# ActiveMoCapDeck_pre.net
KiCad netlist of a schematic drawn in EasyEDA Pro
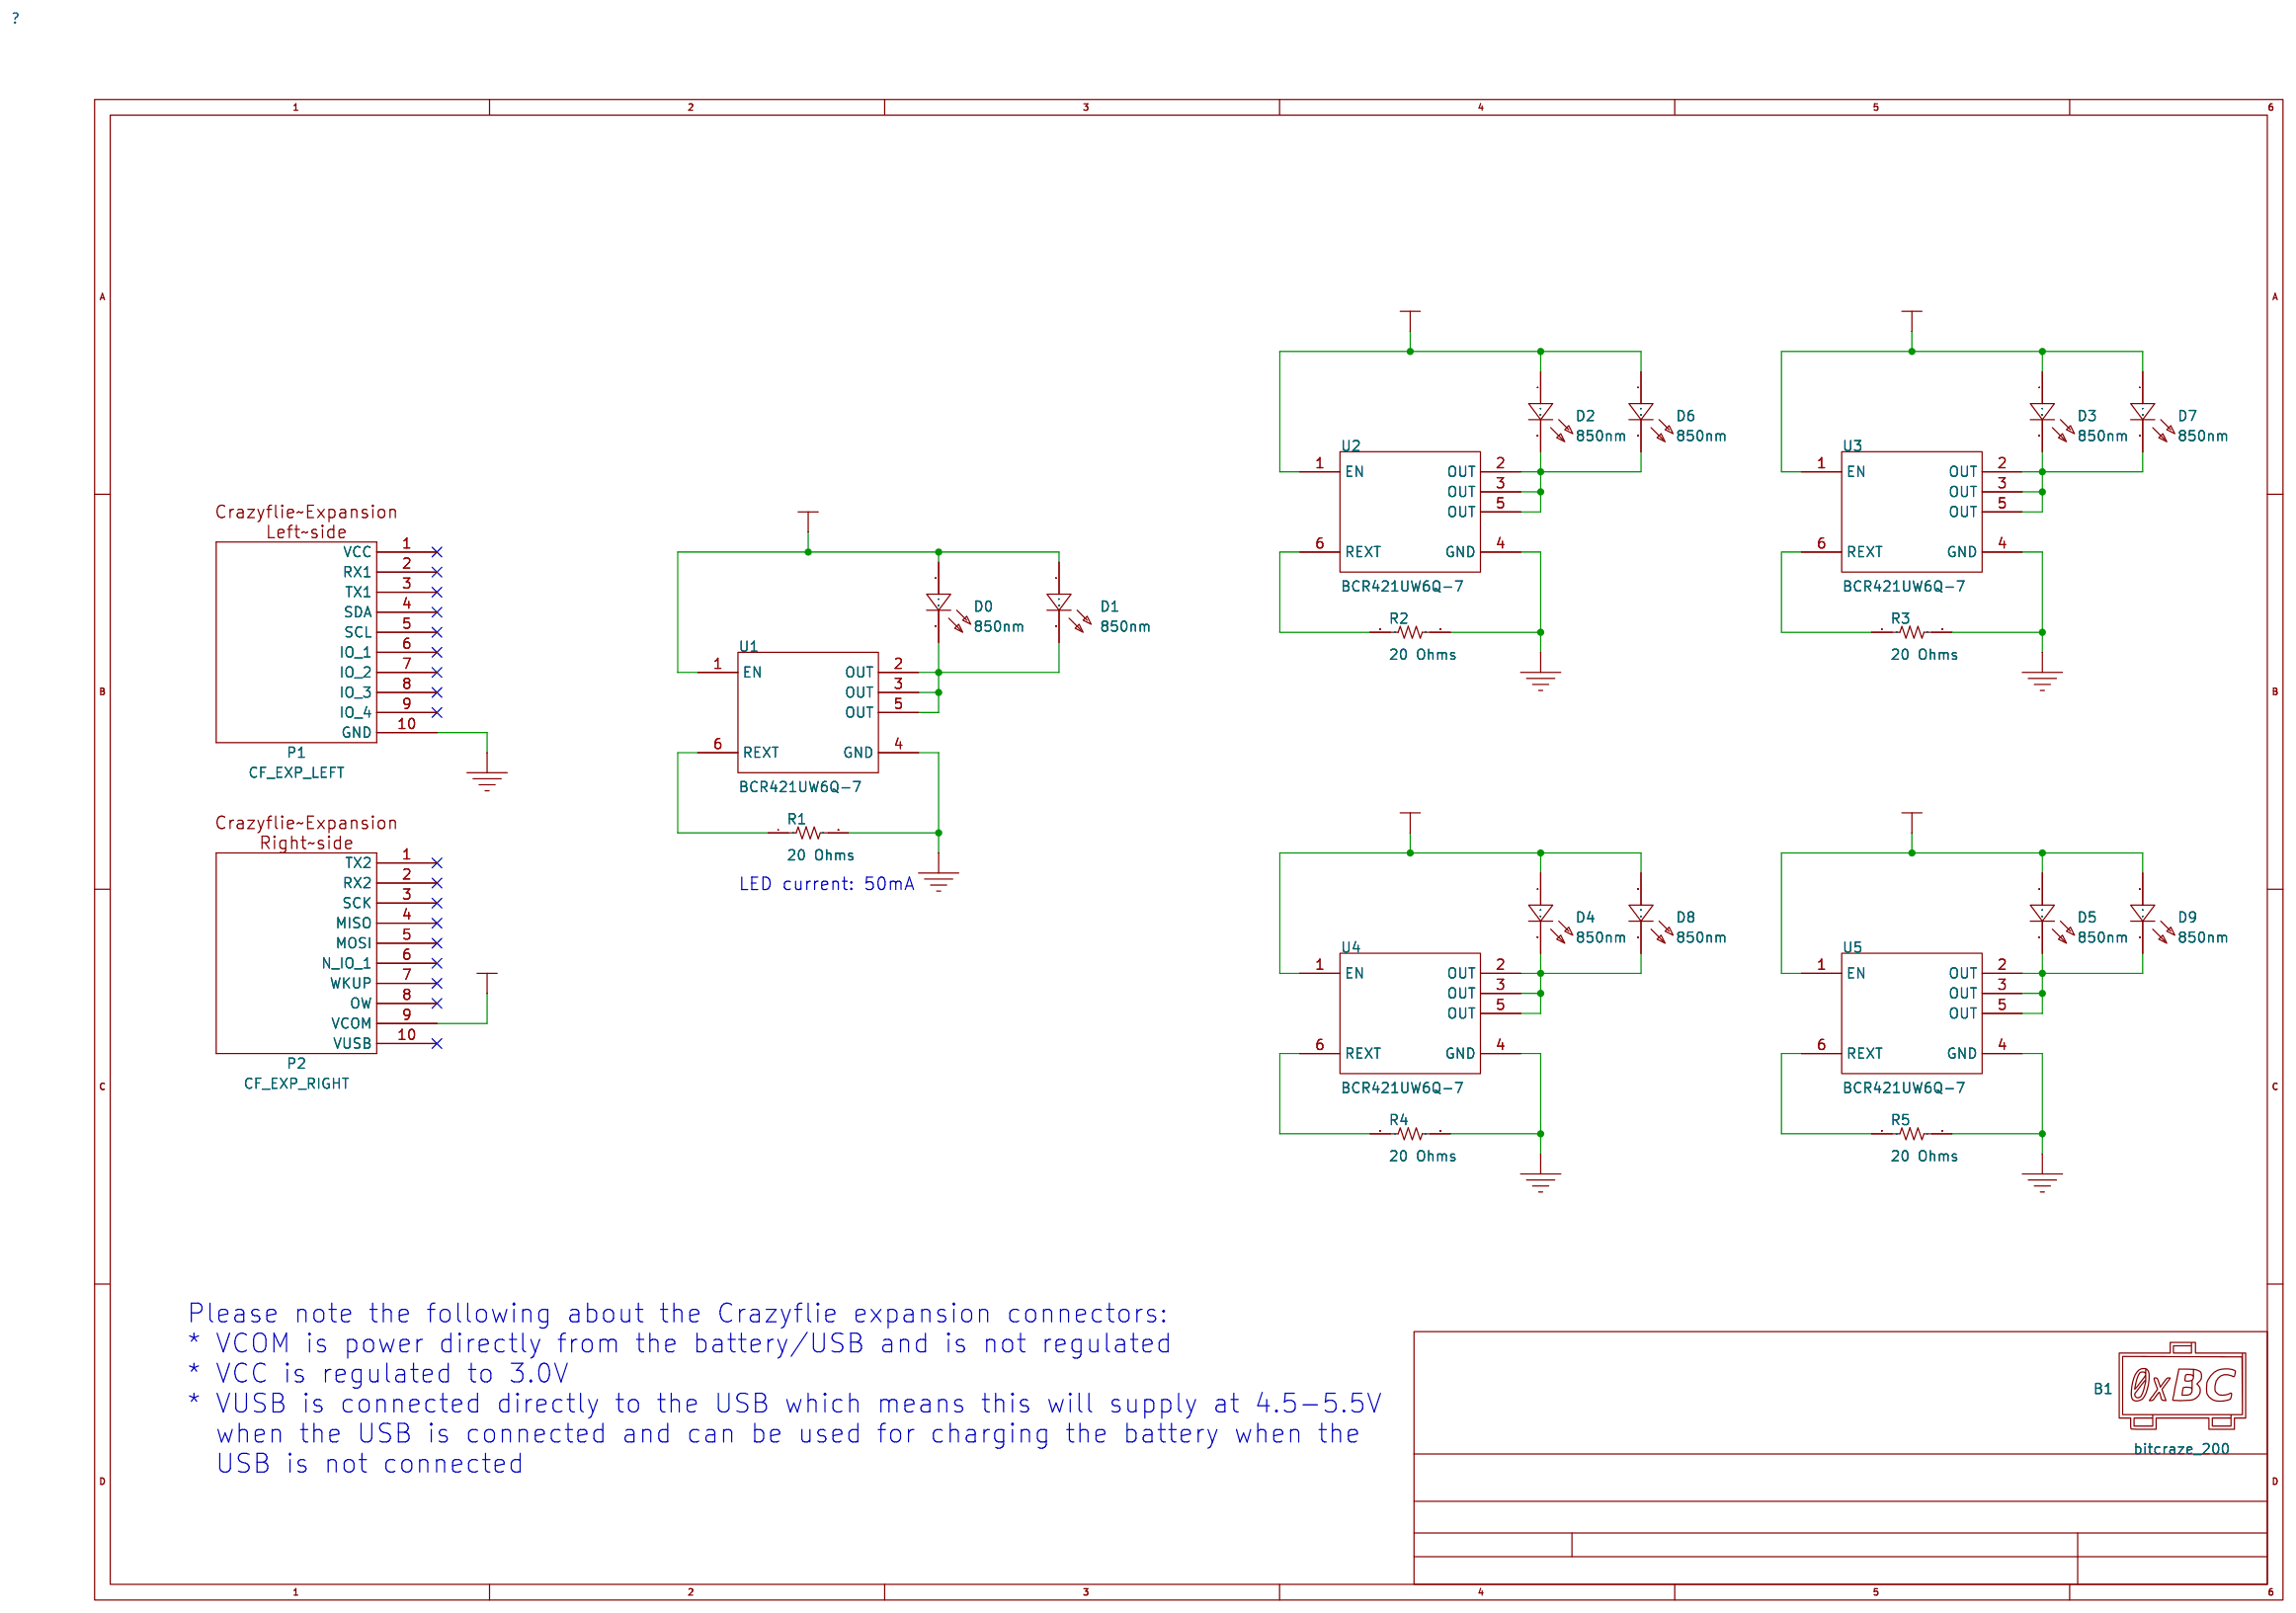
[diagram p0: schematic sheet]

(export (version "E")
  (design (tool "Eeschema 10.0.6"))
  (components
    (comp (ref "B1") (value "bitcraze_200") (libsource (lib "easyedapro") (part "bitcraze_200")))
    (comp (ref "D0")
      (value "Red")
      (description "LED RED SMD")
      (fields (field (name "Manufacturer") "Citizen"))
      (libsource (lib "easyedapro") (part "LED"))
    )
    (comp (ref "D1")
      (value "Red")
      (description "LED RED SMD")
      (fields (field (name "Manufacturer") "Citizen"))
      (libsource (lib "easyedapro") (part "LED"))
    )
    (comp (ref "D2")
      (value "Red")
      (description "LED RED SMD")
      (fields (field (name "Manufacturer") "Citizen"))
      (libsource (lib "easyedapro") (part "LED"))
    )
    (comp (ref "D3")
      (value "Red")
      (description "LED RED SMD")
      (fields (field (name "Manufacturer") "Citizen"))
      (libsource (lib "easyedapro") (part "LED"))
    )
    (comp (ref "D4")
      (value "Red")
      (description "LED RED SMD")
      (fields (field (name "Manufacturer") "Citizen"))
      (libsource (lib "easyedapro") (part "LED"))
    )
    (comp (ref "D5")
      (value "Red")
      (description "LED RED SMD")
      (fields (field (name "Manufacturer") "Citizen"))
      (libsource (lib "easyedapro") (part "LED"))
    )
    (comp (ref "D6")
      (value "Red")
      (description "LED RED SMD")
      (fields (field (name "Manufacturer") "Citizen"))
      (libsource (lib "easyedapro") (part "LED"))
    )
    (comp (ref "D7")
      (value "Red")
      (description "LED RED SMD")
      (fields (field (name "Manufacturer") "Citizen"))
      (libsource (lib "easyedapro") (part "LED"))
    )
    (comp (ref "D8")
      (value "Red")
      (description "LED RED SMD")
      (fields (field (name "Manufacturer") "Citizen"))
      (libsource (lib "easyedapro") (part "LED"))
    )
    (comp (ref "D9")
      (value "Red")
      (description "LED RED SMD")
      (fields (field (name "Manufacturer") "Citizen"))
      (libsource (lib "easyedapro") (part "LED"))
    )
    (comp (ref "P1") (value "CF_EXP_LEFT") (libsource (lib "easyedapro") (part "CF_EXP_LEFT")))
    (comp (ref "P2") (value "CF_EXP_RIGHT") (libsource (lib "easyedapro") (part "CF_EXP_RIGHT")))
    (comp (ref "R1")
      (value "20 Ohms")
      (description "RES 20 OHM 5% 1/10W 0603")
      (fields (field (name "Manufacturer") "Yageo"))
      (libsource (lib "easyedapro") (part "Resistor"))
    )
    (comp (ref "R2")
      (value "20 Ohms")
      (description "RES 20 OHM 5% 1/10W 0603")
      (fields (field (name "Manufacturer") "Yageo"))
      (libsource (lib "easyedapro") (part "Resistor"))
    )
    (comp (ref "R3")
      (value "20 Ohms")
      (description "RES 20 OHM 5% 1/10W 0603")
      (fields (field (name "Manufacturer") "Yageo"))
      (libsource (lib "easyedapro") (part "Resistor"))
    )
    (comp (ref "R4")
      (value "20 Ohms")
      (description "RES 20 OHM 5% 1/10W 0603")
      (fields (field (name "Manufacturer") "Yageo"))
      (libsource (lib "easyedapro") (part "Resistor"))
    )
    (comp (ref "R5")
      (value "20 Ohms")
      (description "RES 20 OHM 5% 1/10W 0603")
      (fields (field (name "Manufacturer") "Yageo"))
      (libsource (lib "easyedapro") (part "Resistor"))
    )
    (comp (ref "U1")
      (value "BCR421UW6Q-7")
      (description "TRANSISTOR LED DRIVER SOT26 T&amp;R")
      (fields (field (name "Manufacturer") "Diodes Inc."))
      (libsource (lib "easyedapro") (part "ad914be0572bb629e6d009380f5a8f4"))
    )
    (comp (ref "U2")
      (value "BCR421UW6Q-7")
      (description "TRANSISTOR LED DRIVER SOT26 T&amp;R")
      (fields (field (name "Manufacturer") "Diodes Inc."))
      (libsource (lib "easyedapro") (part "ad914be0572bb629e6d009380f5a8f4"))
    )
    (comp (ref "U3")
      (value "BCR421UW6Q-7")
      (description "TRANSISTOR LED DRIVER SOT26 T&amp;R")
      (fields (field (name "Manufacturer") "Diodes Inc."))
      (libsource (lib "easyedapro") (part "ad914be0572bb629e6d009380f5a8f4"))
    )
    (comp (ref "U4")
      (value "BCR421UW6Q-7")
      (description "TRANSISTOR LED DRIVER SOT26 T&amp;R")
      (fields (field (name "Manufacturer") "Diodes Inc."))
      (libsource (lib "easyedapro") (part "ad914be0572bb629e6d009380f5a8f4"))
    )
    (comp (ref "U5")
      (value "BCR421UW6Q-7")
      (description "TRANSISTOR LED DRIVER SOT26 T&amp;R")
      (fields (field (name "Manufacturer") "Diodes Inc."))
      (libsource (lib "easyedapro") (part "ad914be0572bb629e6d009380f5a8f4"))
    )
  )
  (nets
    (net (code "1") (name "GND") (class "Default")
      (node (ref "P1") (pin "10") (pinfunction "GND_10") (pintype "unspecified"))
      (node (ref "R1") (pin "2") (pinfunction "2_2") (pintype "unspecified"))
      (node (ref "R2") (pin "2") (pinfunction "2_2") (pintype "unspecified"))
      (node (ref "R3") (pin "2") (pinfunction "2_2") (pintype "unspecified"))
      (node (ref "R4") (pin "2") (pinfunction "2_2") (pintype "unspecified"))
      (node (ref "R5") (pin "2") (pinfunction "2_2") (pintype "unspecified"))
      (node (ref "U1") (pin "4") (pinfunction "GND_4") (pintype "unspecified"))
      (node (ref "U2") (pin "4") (pinfunction "GND_4") (pintype "unspecified"))
      (node (ref "U3") (pin "4") (pinfunction "GND_4") (pintype "unspecified"))
      (node (ref "U4") (pin "4") (pinfunction "GND_4") (pintype "unspecified"))
      (node (ref "U5") (pin "4") (pinfunction "GND_4") (pintype "unspecified"))
    )
    (net (code "2") (name "Net-(D0-Pad2)") (class "Default")
      (node (ref "D0") (pin "2") (pinfunction "2_2") (pintype "unspecified"))
      (node (ref "D1") (pin "2") (pinfunction "2_2") (pintype "unspecified"))
      (node (ref "U1") (pin "2") (pinfunction "OUT_2") (pintype "unspecified"))
      (node (ref "U1") (pin "3") (pinfunction "OUT_3") (pintype "unspecified"))
      (node (ref "U1") (pin "5") (pinfunction "OUT_5") (pintype "unspecified"))
    )
    (net (code "3") (name "Net-(D2-Pad2)") (class "Default")
      (node (ref "D2") (pin "2") (pinfunction "2_2") (pintype "unspecified"))
      (node (ref "D6") (pin "2") (pinfunction "2_2") (pintype "unspecified"))
      (node (ref "U2") (pin "2") (pinfunction "OUT_2") (pintype "unspecified"))
      (node (ref "U2") (pin "3") (pinfunction "OUT_3") (pintype "unspecified"))
      (node (ref "U2") (pin "5") (pinfunction "OUT_5") (pintype "unspecified"))
    )
    (net (code "4") (name "Net-(D3-Pad2)") (class "Default")
      (node (ref "D3") (pin "2") (pinfunction "2_2") (pintype "unspecified"))
      (node (ref "D7") (pin "2") (pinfunction "2_2") (pintype "unspecified"))
      (node (ref "U3") (pin "2") (pinfunction "OUT_2") (pintype "unspecified"))
      (node (ref "U3") (pin "3") (pinfunction "OUT_3") (pintype "unspecified"))
      (node (ref "U3") (pin "5") (pinfunction "OUT_5") (pintype "unspecified"))
    )
    (net (code "5") (name "Net-(D4-Pad2)") (class "Default")
      (node (ref "D4") (pin "2") (pinfunction "2_2") (pintype "unspecified"))
      (node (ref "D8") (pin "2") (pinfunction "2_2") (pintype "unspecified"))
      (node (ref "U4") (pin "2") (pinfunction "OUT_2") (pintype "unspecified"))
      (node (ref "U4") (pin "3") (pinfunction "OUT_3") (pintype "unspecified"))
      (node (ref "U4") (pin "5") (pinfunction "OUT_5") (pintype "unspecified"))
    )
    (net (code "6") (name "Net-(D5-Pad2)") (class "Default")
      (node (ref "D5") (pin "2") (pinfunction "2_2") (pintype "unspecified"))
      (node (ref "D9") (pin "2") (pinfunction "2_2") (pintype "unspecified"))
      (node (ref "U5") (pin "2") (pinfunction "OUT_2") (pintype "unspecified"))
      (node (ref "U5") (pin "3") (pinfunction "OUT_3") (pintype "unspecified"))
      (node (ref "U5") (pin "5") (pinfunction "OUT_5") (pintype "unspecified"))
    )
    (net (code "7") (name "Net-(U1-REXT)") (class "Default")
      (node (ref "R1") (pin "1") (pinfunction "1_1") (pintype "unspecified"))
      (node (ref "U1") (pin "6") (pinfunction "REXT_6") (pintype "unspecified"))
    )
    (net (code "8") (name "Net-(U2-REXT)") (class "Default")
      (node (ref "R2") (pin "1") (pinfunction "1_1") (pintype "unspecified"))
      (node (ref "U2") (pin "6") (pinfunction "REXT_6") (pintype "unspecified"))
    )
    (net (code "9") (name "Net-(U3-REXT)") (class "Default")
      (node (ref "R3") (pin "1") (pinfunction "1_1") (pintype "unspecified"))
      (node (ref "U3") (pin "6") (pinfunction "REXT_6") (pintype "unspecified"))
    )
    (net (code "10") (name "Net-(U4-REXT)") (class "Default")
      (node (ref "R4") (pin "1") (pinfunction "1_1") (pintype "unspecified"))
      (node (ref "U4") (pin "6") (pinfunction "REXT_6") (pintype "unspecified"))
    )
    (net (code "11") (name "Net-(U5-REXT)") (class "Default")
      (node (ref "R5") (pin "1") (pinfunction "1_1") (pintype "unspecified"))
      (node (ref "U5") (pin "6") (pinfunction "REXT_6") (pintype "unspecified"))
    )
    (net (code "12") (name "VCOM") (class "Default")
      (node (ref "D0") (pin "1") (pinfunction "1_1") (pintype "unspecified"))
      (node (ref "D1") (pin "1") (pinfunction "1_1") (pintype "unspecified"))
      (node (ref "D2") (pin "1") (pinfunction "1_1") (pintype "unspecified"))
      (node (ref "D3") (pin "1") (pinfunction "1_1") (pintype "unspecified"))
      (node (ref "D4") (pin "1") (pinfunction "1_1") (pintype "unspecified"))
      (node (ref "D5") (pin "1") (pinfunction "1_1") (pintype "unspecified"))
      (node (ref "D6") (pin "1") (pinfunction "1_1") (pintype "unspecified"))
      (node (ref "D7") (pin "1") (pinfunction "1_1") (pintype "unspecified"))
      (node (ref "D8") (pin "1") (pinfunction "1_1") (pintype "unspecified"))
      (node (ref "D9") (pin "1") (pinfunction "1_1") (pintype "unspecified"))
      (node (ref "P2") (pin "9") (pinfunction "VCOM_9") (pintype "unspecified"))
      (node (ref "U1") (pin "1") (pinfunction "EN_1") (pintype "input"))
      (node (ref "U2") (pin "1") (pinfunction "EN_1") (pintype "input"))
      (node (ref "U3") (pin "1") (pinfunction "EN_1") (pintype "input"))
      (node (ref "U4") (pin "1") (pinfunction "EN_1") (pintype "input"))
      (node (ref "U5") (pin "1") (pinfunction "EN_1") (pintype "input"))
    )
    (net (code "13") (name "unconnected-(P1-IO_1-Pad6)") (class "Default")
      (node (ref "P1") (pin "6") (pinfunction "IO_1_6") (pintype "unspecified+no_connect"))
    )
    (net (code "14") (name "unconnected-(P1-IO_2-Pad7)") (class "Default")
      (node (ref "P1") (pin "7") (pinfunction "IO_2_7") (pintype "unspecified+no_connect"))
    )
    (net (code "15") (name "unconnected-(P1-IO_3-Pad8)") (class "Default")
      (node (ref "P1") (pin "8") (pinfunction "IO_3_8") (pintype "unspecified+no_connect"))
    )
    (net (code "16") (name "unconnected-(P1-IO_4-Pad9)") (class "Default")
      (node (ref "P1") (pin "9") (pinfunction "IO_4_9") (pintype "unspecified+no_connect"))
    )
    (net (code "17") (name "unconnected-(P1-RX1-Pad2)") (class "Default")
      (node (ref "P1") (pin "2") (pinfunction "RX1_2") (pintype "unspecified+no_connect"))
    )
    (net (code "18") (name "unconnected-(P1-SCL-Pad5)") (class "Default")
      (node (ref "P1") (pin "5") (pinfunction "SCL_5") (pintype "unspecified+no_connect"))
    )
    (net (code "19") (name "unconnected-(P1-SDA-Pad4)") (class "Default")
      (node (ref "P1") (pin "4") (pinfunction "SDA_4") (pintype "unspecified+no_connect"))
    )
    (net (code "20") (name "unconnected-(P1-TX1-Pad3)") (class "Default")
      (node (ref "P1") (pin "3") (pinfunction "TX1_3") (pintype "unspecified+no_connect"))
    )
    (net (code "21") (name "unconnected-(P1-VCC-Pad1)") (class "Default")
      (node (ref "P1") (pin "1") (pinfunction "VCC_1") (pintype "unspecified+no_connect"))
    )
    (net (code "22") (name "unconnected-(P2-MISO-Pad4)") (class "Default")
      (node (ref "P2") (pin "4") (pinfunction "MISO_4") (pintype "unspecified+no_connect"))
    )
    (net (code "23") (name "unconnected-(P2-MOSI-Pad5)") (class "Default")
      (node (ref "P2") (pin "5") (pinfunction "MOSI_5") (pintype "unspecified+no_connect"))
    )
    (net (code "24") (name "unconnected-(P2-N_IO_1-Pad6)") (class "Default")
      (node (ref "P2") (pin "6") (pinfunction "N_IO_1_6") (pintype "unspecified+no_connect"))
    )
    (net (code "25") (name "unconnected-(P2-OW-Pad8)") (class "Default")
      (node (ref "P2") (pin "8") (pinfunction "OW_8") (pintype "unspecified+no_connect"))
    )
    (net (code "26") (name "unconnected-(P2-RX2-Pad2)") (class "Default")
      (node (ref "P2") (pin "2") (pinfunction "RX2_2") (pintype "unspecified+no_connect"))
    )
    (net (code "27") (name "unconnected-(P2-SCK-Pad3)") (class "Default")
      (node (ref "P2") (pin "3") (pinfunction "SCK_3") (pintype "unspecified+no_connect"))
    )
    (net (code "28") (name "unconnected-(P2-TX2-Pad1)") (class "Default")
      (node (ref "P2") (pin "1") (pinfunction "TX2_1") (pintype "unspecified+no_connect"))
    )
    (net (code "29") (name "unconnected-(P2-VUSB-Pad10)") (class "Default")
      (node (ref "P2") (pin "10") (pinfunction "VUSB_10") (pintype "unspecified+no_connect"))
    )
    (net (code "30") (name "unconnected-(P2-WKUP-Pad7)") (class "Default")
      (node (ref "P2") (pin "7") (pinfunction "WKUP_7") (pintype "unspecified+no_connect"))
    )
  )
)
